# SenseBox-MCU-2-1.net
KiCad netlist of a schematic drawn in EAGLE
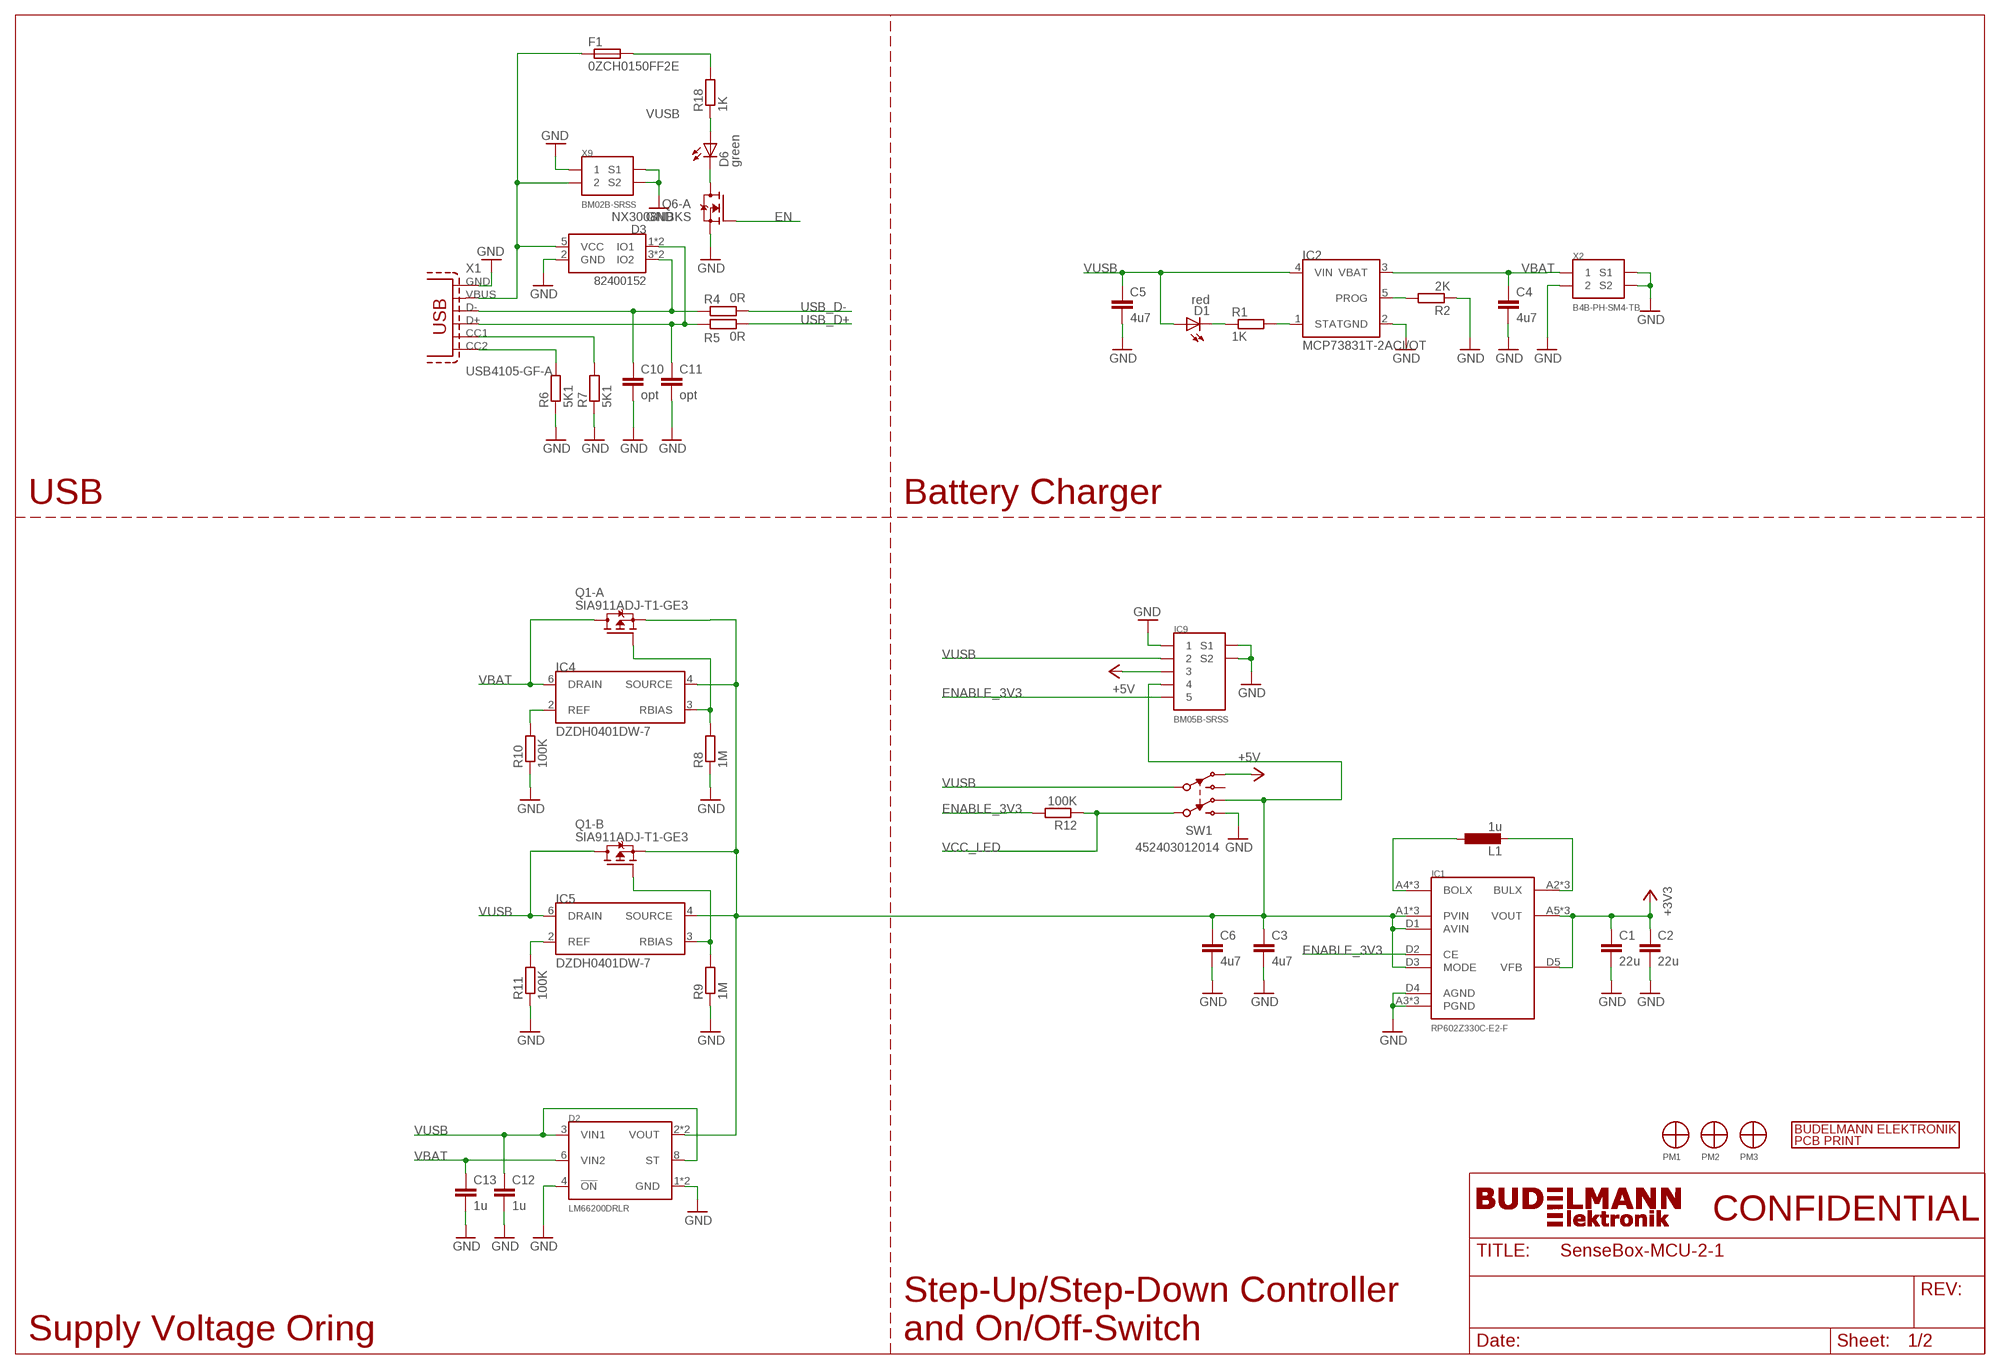
[diagram p0: schematic, sheet 1]
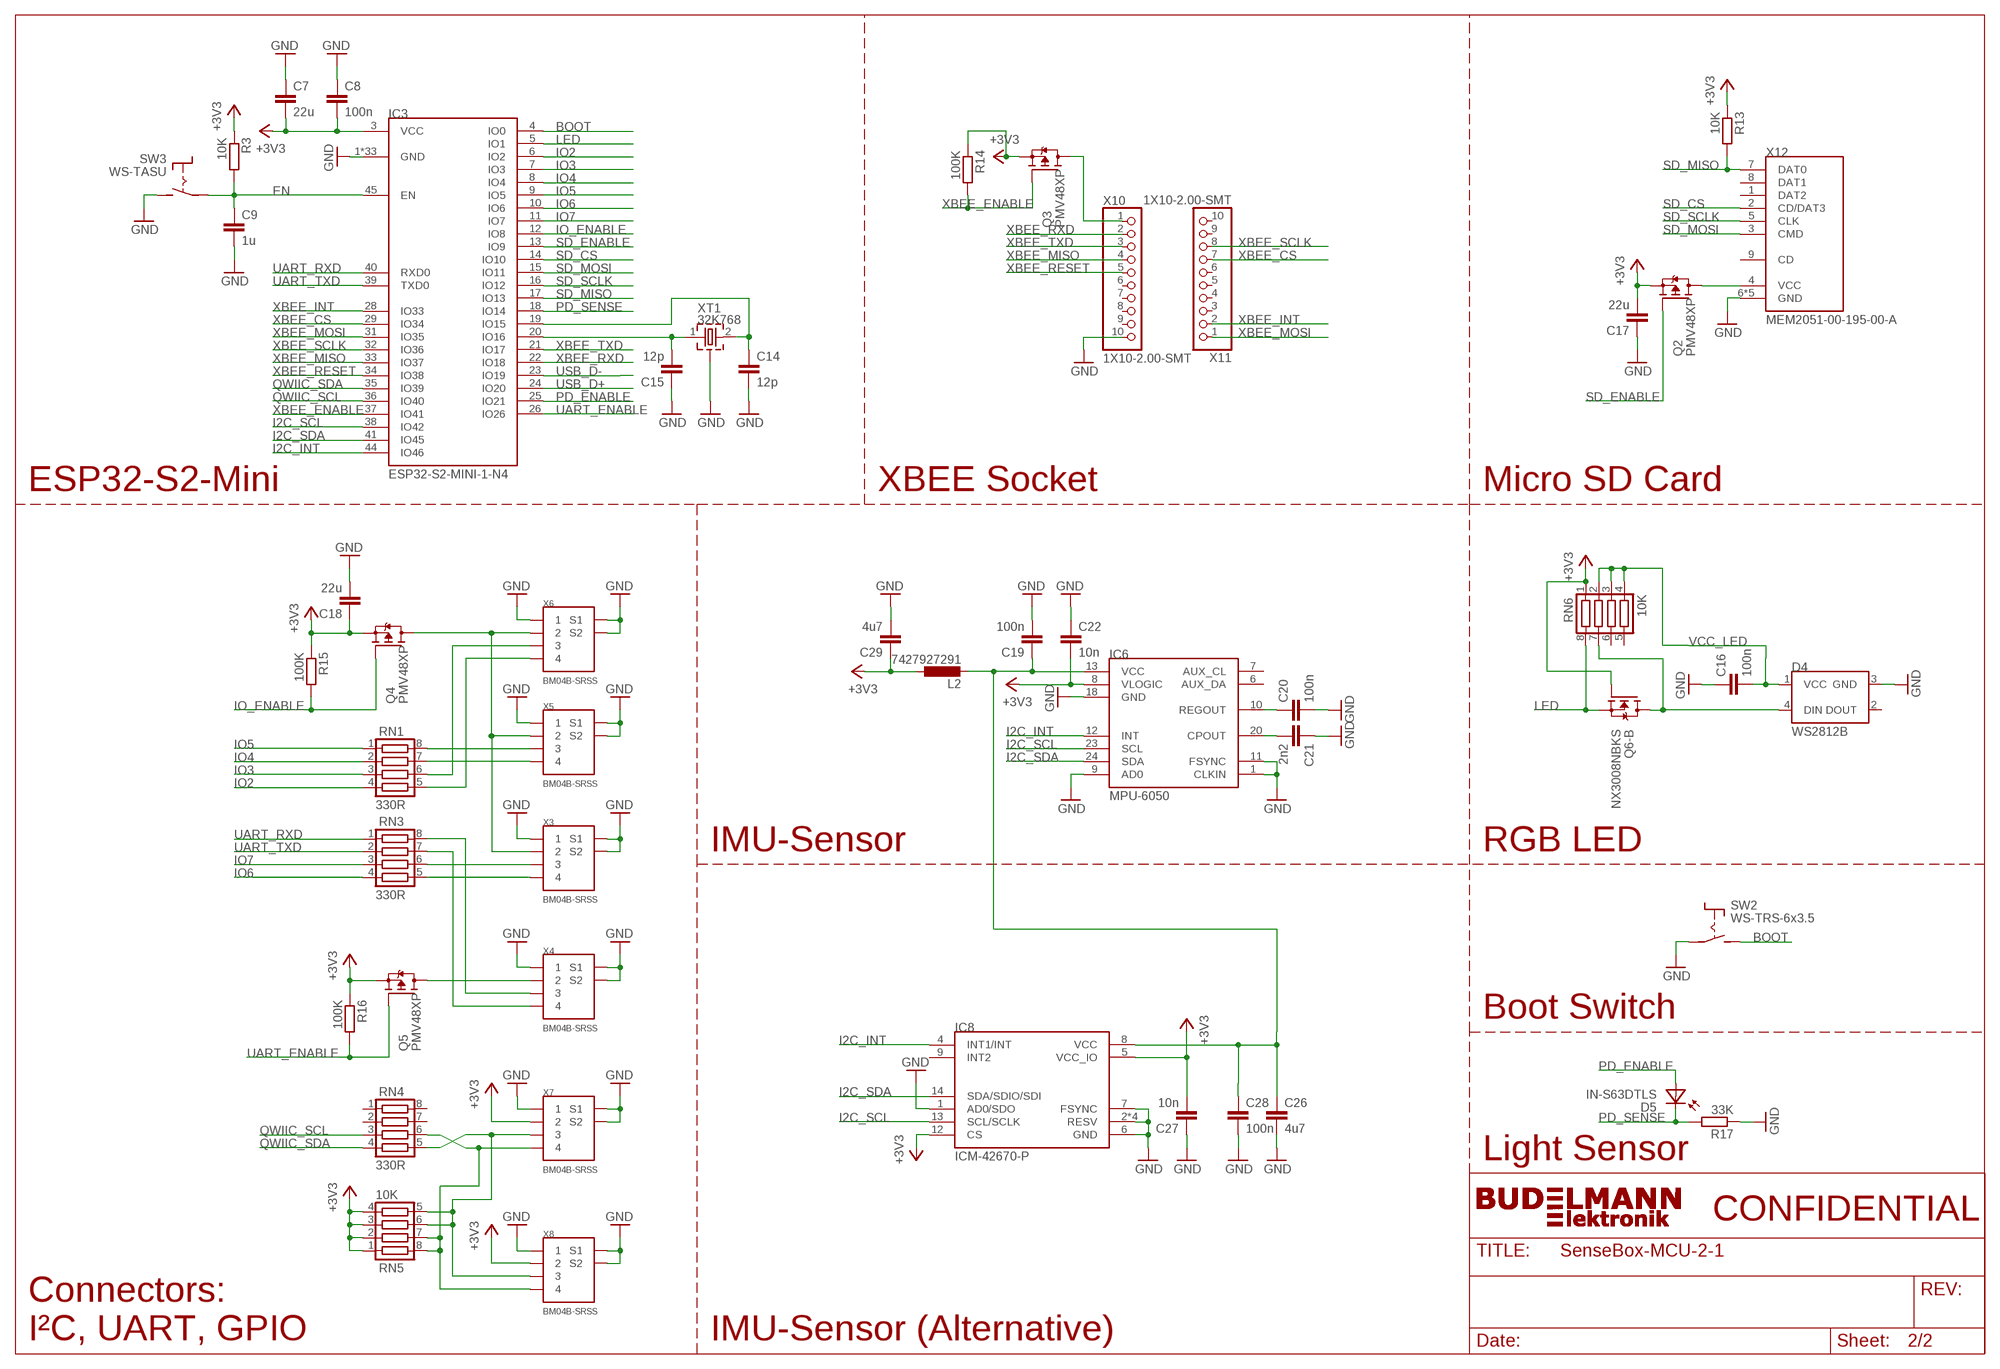
[diagram p1: schematic, sheet 2]

(export (version "E")
  (design (tool "Eeschema 10.0.6"))
  (components
    (comp (ref "C7")
      (value "22u")
      (footprint "eagle-import:0805N")
      (fields (field (name "VOLTAGE") "6V3"))
      (libsource (lib "eagle-import") (part "C_0805N_22U"))
    )
    (comp (ref "C8")
      (value "100n")
      (footprint "eagle-import:0402N")
      (fields (field (name "VOLTAGE") "16"))
      (libsource (lib "eagle-import") (part "C_0402N_100N"))
    )
    (comp (ref "C9")
      (value "1u")
      (footprint "eagle-import:0402N")
      (fields (field (name "VOLTAGE") "10"))
      (libsource (lib "eagle-import") (part "C_0402N_1U"))
    )
    (comp (ref "C14")
      (value "12p")
      (footprint "eagle-import:0402N")
      (fields (field (name "VOLTAGE") "50"))
      (libsource (lib "eagle-import") (part "C_0402N_12P"))
    )
    (comp (ref "C15")
      (value "12p")
      (footprint "eagle-import:0402N")
      (fields (field (name "VOLTAGE") "50"))
      (libsource (lib "eagle-import") (part "C_0402N_12P"))
    )
    (comp (ref "C16")
      (value "100n")
      (footprint "eagle-import:0402N")
      (fields (field (name "VOLTAGE") "16"))
      (libsource (lib "eagle-import") (part "C_0402N_100N"))
    )
    (comp (ref "C17")
      (value "22u")
      (footprint "eagle-import:0805N")
      (fields (field (name "VOLTAGE") "6V3"))
      (libsource (lib "eagle-import") (part "C_0805N_22U"))
    )
    (comp (ref "C18")
      (value "22u")
      (footprint "eagle-import:0805N")
      (fields (field (name "VOLTAGE") "6V3"))
      (libsource (lib "eagle-import") (part "C_0805N_22U"))
    )
    (comp (ref "C19")
      (value "100n")
      (footprint "eagle-import:0402N")
      (fields (field (name "VOLTAGE") "16"))
      (libsource (lib "eagle-import") (part "C_0402N_100N"))
    )
    (comp (ref "C20")
      (value "100n")
      (footprint "eagle-import:0402N")
      (fields (field (name "VOLTAGE") "16"))
      (libsource (lib "eagle-import") (part "C_0402N_100N"))
    )
    (comp (ref "C21")
      (value "2n2")
      (footprint "eagle-import:0402N")
      (fields (field (name "VOLTAGE") "50"))
      (libsource (lib "eagle-import") (part "C_0402N_2N2"))
    )
    (comp (ref "C22")
      (value "10n")
      (footprint "eagle-import:0402N")
      (fields (field (name "VOLTAGE") "25"))
      (libsource (lib "eagle-import") (part "C_0402N_10N"))
    )
    (comp (ref "C26")
      (value "4u7")
      (footprint "eagle-import:0603N")
      (fields (field (name "VOLTAGE") "6V3"))
      (libsource (lib "eagle-import") (part "C_0603N_4U7"))
    )
    (comp (ref "C27")
      (value "10n")
      (footprint "eagle-import:0402N")
      (fields (field (name "VOLTAGE") "25"))
      (libsource (lib "eagle-import") (part "C_0402N_10N"))
    )
    (comp (ref "C28")
      (value "100n")
      (footprint "eagle-import:0402N")
      (fields (field (name "VOLTAGE") "16"))
      (libsource (lib "eagle-import") (part "C_0402N_100N"))
    )
    (comp (ref "C29")
      (value "4u7")
      (footprint "eagle-import:0603N")
      (fields (field (name "VOLTAGE") "6V3"))
      (libsource (lib "eagle-import") (part "C_0603N_4U7"))
    )
    (comp (ref "D4")
      (value "WS2812B")
      (footprint "eagle-import:5050")
      (libsource (lib "eagle-import") (part "LED-ADRESSABLE_5050_WS2812B"))
    )
    (comp (ref "D5")
      (value "IN-S63DTLS")
      (footprint "eagle-import:0603N")
      (libsource (lib "eagle-import") (part "PHOTODIODE_0603N_IN-S63DTLS"))
    )
    (comp (ref "IC3")
      (value "ESP32-S2-MINI-1-N4")
      (footprint "eagle-import:ESP32-S2-MINI")
      (libsource (lib "eagle-import") (part "ESP32-S2-MINI_ESP32-S2-MINI_ESP32-S2-MINI-1-N4"))
    )
    (comp (ref "IC6")
      (value "MPU-6050")
      (footprint "eagle-import:QFN24_4X4")
      (libsource (lib "eagle-import") (part "MPU-6050"))
    )
    (comp (ref "IC8")
      (value "ICM-42670-P")
      (footprint "eagle-import:LGA14_2.5X3")
      (libsource (lib "eagle-import") (part "ICM-42670-P_LGA14_2.5X3"))
    )
    (comp (ref "L2")
      (value "7427927291")
      (footprint "eagle-import:0402N")
      (libsource (lib "eagle-import") (part "L_0402N_WE-CBF-7427927291"))
    )
    (comp (ref "Q2")
      (value "PMV48XP")
      (footprint "eagle-import:SOT23")
      (fields (field (name "VOLTAGE") "20"))
      (libsource (lib "eagle-import") (part "MOSFET-P_SOT23'_PMV48XP"))
    )
    (comp (ref "Q3")
      (value "PMV48XP")
      (footprint "eagle-import:SOT23")
      (fields (field (name "VOLTAGE") "20"))
      (libsource (lib "eagle-import") (part "MOSFET-P_SOT23'_PMV48XP"))
    )
    (comp (ref "Q4")
      (value "PMV48XP")
      (footprint "eagle-import:SOT23")
      (fields (field (name "VOLTAGE") "20"))
      (libsource (lib "eagle-import") (part "MOSFET-P_SOT23'_PMV48XP"))
    )
    (comp (ref "Q5")
      (value "PMV48XP")
      (footprint "eagle-import:SOT23")
      (fields (field (name "VOLTAGE") "20"))
      (libsource (lib "eagle-import") (part "MOSFET-P_SOT23'_PMV48XP"))
    )
    (comp (ref "Q6")
      (value "NX3008NBKS")
      (footprint "eagle-import:SOT363")
      (fields (field (name "POWER") "0.3") (field (name "VOLTAGE") "30"))
      (libsource (lib "eagle-import") (part "MOSFET-N-DUAL_SOT363_NX3008NBKS"))
    )
    (comp (ref "R3")
      (value "10K")
      (footprint "eagle-import:0402N")
      (fields (field (name "POWER") "0.063") (field (name "TOLERANCE") "1%") (field (name "VOLTAGE") "50"))
      (libsource (lib "eagle-import") (part "R_0402N_10K"))
    )
    (comp (ref "R13")
      (value "10K")
      (footprint "eagle-import:0402N")
      (fields (field (name "POWER") "0.063") (field (name "TOLERANCE") "1%") (field (name "VOLTAGE") "50"))
      (libsource (lib "eagle-import") (part "R_0402N_10K"))
    )
    (comp (ref "R14")
      (value "100K")
      (footprint "eagle-import:0402N")
      (fields (field (name "POWER") "0.063") (field (name "TOLERANCE") "1%") (field (name "VOLTAGE") "50"))
      (libsource (lib "eagle-import") (part "R_0402N_100K"))
    )
    (comp (ref "R15")
      (value "100K")
      (footprint "eagle-import:0402N")
      (fields (field (name "POWER") "0.063") (field (name "TOLERANCE") "1%") (field (name "VOLTAGE") "50"))
      (libsource (lib "eagle-import") (part "R_0402N_100K"))
    )
    (comp (ref "R16")
      (value "100K")
      (footprint "eagle-import:0402N")
      (fields (field (name "POWER") "0.063") (field (name "TOLERANCE") "1%") (field (name "VOLTAGE") "50"))
      (libsource (lib "eagle-import") (part "R_0402N_100K"))
    )
    (comp (ref "R17")
      (value "33K")
      (footprint "eagle-import:0402N")
      (fields (field (name "POWER") "0.063") (field (name "TOLERANCE") "1%") (field (name "VOLTAGE") "50"))
      (libsource (lib "eagle-import") (part "R_0402N_33K"))
    )
    (comp (ref "RN1")
      (value "330R")
      (footprint "eagle-import:CAY16")
      (fields (field (name "POWER") "0.062") (field (name "TOLERANCE") "5%") (field (name "VOLTAGE") "50"))
      (libsource (lib "eagle-import") (part "RN4_CAY16_330R"))
    )
    (comp (ref "RN3")
      (value "330R")
      (footprint "eagle-import:CAY16")
      (fields (field (name "POWER") "0.062") (field (name "TOLERANCE") "5%") (field (name "VOLTAGE") "50"))
      (libsource (lib "eagle-import") (part "RN4_CAY16_330R"))
    )
    (comp (ref "RN4")
      (value "330R")
      (footprint "eagle-import:CAY16")
      (fields (field (name "POWER") "0.062") (field (name "TOLERANCE") "5%") (field (name "VOLTAGE") "50"))
      (libsource (lib "eagle-import") (part "RN4_CAY16_330R"))
    )
    (comp (ref "RN5")
      (value "10K")
      (footprint "eagle-import:CAY16")
      (fields (field (name "POWER") "0.062") (field (name "TOLERANCE") "5%") (field (name "VOLTAGE") "50"))
      (libsource (lib "eagle-import") (part "RN4_CAY16_10K"))
    )
    (comp (ref "RN6")
      (value "10K")
      (footprint "eagle-import:CAY16")
      (fields (field (name "POWER") "0.062") (field (name "TOLERANCE") "5%") (field (name "VOLTAGE") "50"))
      (libsource (lib "eagle-import") (part "RN4_CAY16_10K"))
    )
    (comp (ref "SW2")
      (value "WS-TRS-6x3.5")
      (footprint "eagle-import:WS-TRS-6X3.5")
      (libsource (lib "eagle-import") (part "TACTILE_SWITCH_WS-TRS-6X3.5"))
    )
    (comp (ref "SW3")
      (value "WS-TASU")
      (footprint "eagle-import:WS-TASU")
      (libsource (lib "eagle-import") (part "TACTILE_SWITCH_WS-TASU"))
    )
    (comp (ref "X3")
      (value "BM04B-SRSS")
      (footprint "eagle-import:BM04B-SRSS")
      (libsource (lib "eagle-import") (part "SH-04_BM04B-SRSS_BM04B-SRSS"))
    )
    (comp (ref "X4")
      (value "BM04B-SRSS")
      (footprint "eagle-import:BM04B-SRSS")
      (libsource (lib "eagle-import") (part "SH-04_BM04B-SRSS_BM04B-SRSS"))
    )
    (comp (ref "X5")
      (value "BM04B-SRSS")
      (footprint "eagle-import:BM04B-SRSS")
      (libsource (lib "eagle-import") (part "SH-04_BM04B-SRSS_BM04B-SRSS"))
    )
    (comp (ref "X6")
      (value "BM04B-SRSS")
      (footprint "eagle-import:BM04B-SRSS")
      (libsource (lib "eagle-import") (part "SH-04_BM04B-SRSS_BM04B-SRSS"))
    )
    (comp (ref "X7")
      (value "BM04B-SRSS")
      (footprint "eagle-import:BM04B-SRSS")
      (libsource (lib "eagle-import") (part "SH-04_BM04B-SRSS_BM04B-SRSS"))
    )
    (comp (ref "X8")
      (value "BM04B-SRSS")
      (footprint "eagle-import:BM04B-SRSS")
      (libsource (lib "eagle-import") (part "SH-04_BM04B-SRSS_BM04B-SRSS"))
    )
    (comp (ref "X10")
      (value "1X10-2.00-SMT")
      (footprint "eagle-import:1X10-2.00-SMD")
      (libsource (lib "eagle-import") (part "1X10_2.00-SMT"))
    )
    (comp (ref "X11")
      (value "1X10-2.00-SMT")
      (footprint "eagle-import:1X10-2.00-SMD")
      (libsource (lib "eagle-import") (part "1X10_2.00-SMT"))
    )
    (comp (ref "X12")
      (value "MEM2051-00-195-00-A")
      (footprint "eagle-import:MEM2051")
      (libsource (lib "eagle-import") (part "SD-CARD2_MEM2051"))
    )
    (comp (ref "XT1")
      (value "32K768")
      (footprint "eagle-import:1.4X1.5X5.2")
      (libsource (lib "eagle-import") (part "CRYSTAL-1GND_1.4X1.5X5.2"))
    )
    (comp (ref "C1")
      (value "22u")
      (footprint "eagle-import:0805N")
      (fields (field (name "VOLTAGE") "6V3"))
      (libsource (lib "eagle-import") (part "C_0805N_22U"))
    )
    (comp (ref "C2")
      (value "22u")
      (footprint "eagle-import:0805N")
      (fields (field (name "VOLTAGE") "6V3"))
      (libsource (lib "eagle-import") (part "C_0805N_22U"))
    )
    (comp (ref "C3")
      (value "4u7")
      (footprint "eagle-import:0603N")
      (fields (field (name "VOLTAGE") "6V3"))
      (libsource (lib "eagle-import") (part "C_0603N_4U7"))
    )
    (comp (ref "C4")
      (value "4u7")
      (footprint "eagle-import:0603N")
      (fields (field (name "VOLTAGE") "6V3"))
      (libsource (lib "eagle-import") (part "C_0603N_4U7"))
    )
    (comp (ref "C5")
      (value "4u7")
      (footprint "eagle-import:0603N")
      (fields (field (name "VOLTAGE") "6V3"))
      (libsource (lib "eagle-import") (part "C_0603N_4U7"))
    )
    (comp (ref "C6")
      (value "4u7")
      (footprint "eagle-import:0603N")
      (fields (field (name "VOLTAGE") "6V3"))
      (libsource (lib "eagle-import") (part "C_0603N_4U7"))
    )
    (comp (ref "C10")
      (value "opt")
      (footprint "eagle-import:0402N")
      (libsource (lib "eagle-import") (part "C_0402N"))
    )
    (comp (ref "C11")
      (value "opt")
      (footprint "eagle-import:0402N")
      (libsource (lib "eagle-import") (part "C_0402N"))
    )
    (comp (ref "C12")
      (value "1u")
      (footprint "eagle-import:0402N")
      (fields (field (name "VOLTAGE") "10"))
      (libsource (lib "eagle-import") (part "C_0402N_1U"))
    )
    (comp (ref "C13")
      (value "1u")
      (footprint "eagle-import:0402N")
      (fields (field (name "VOLTAGE") "10"))
      (libsource (lib "eagle-import") (part "C_0402N_1U"))
    )
    (comp (ref "D1")
      (value "red")
      (footprint "eagle-import:0603N")
      (libsource (lib "eagle-import") (part "LED_0603N_RED"))
    )
    (comp (ref "D2")
      (value "LM66200DRLR")
      (footprint "eagle-import:SOT-5X3")
      (libsource (lib "eagle-import") (part "LM66200"))
    )
    (comp (ref "D3")
      (value "82400152")
      (footprint "eagle-import:SOT563")
      (libsource (lib "eagle-import") (part "TVS-3-CHANNELS_SOT563_WE-TVS"))
    )
    (comp (ref "D6")
      (value "green")
      (footprint "eagle-import:0603N")
      (libsource (lib "eagle-import") (part "LED_0603N_GREEN"))
    )
    (comp (ref "F1")
      (value "0ZCH0150FF2E")
      (footprint "eagle-import:1210N")
      (libsource (lib "eagle-import") (part "FUSE-2PIN_1210N_1.5A"))
    )
    (comp (ref "IC1")
      (value "RP602Z330C-E2-F")
      (footprint "eagle-import:WLCSP-20-P1")
      (libsource (lib "eagle-import") (part "RP602_WLCSP-20-P1_RP602Z330C-E2-F"))
    )
    (comp (ref "IC2")
      (value "MCP73831T-2ACI/OT")
      (footprint "eagle-import:SOT23-5")
      (libsource (lib "eagle-import") (part "MCP73831_SOT23-5_MCP73831T-2ACI/OT"))
    )
    (comp (ref "IC4")
      (value "DZDH0401DW-7")
      (footprint "eagle-import:SOT363")
      (libsource (lib "eagle-import") (part "DZDH0401DW"))
    )
    (comp (ref "IC5")
      (value "DZDH0401DW-7")
      (footprint "eagle-import:SOT363")
      (libsource (lib "eagle-import") (part "DZDH0401DW"))
    )
    (comp (ref "IC9")
      (value "BM05B-SRSS")
      (footprint "eagle-import:BM05B-SRSS")
      (libsource (lib "eagle-import") (part "SH-05_BM05B-SRSS_BM05B-SRSS"))
    )
    (comp (ref "L1")
      (value "1u")
      (footprint "eagle-import:5040")
      (libsource (lib "eagle-import") (part "L_5040_WE-LQS-1U"))
    )
    (comp (ref "PM1")
      (value "PM_ASSEMBLY")
      (footprint "eagle-import:PM1")
      (libsource (lib "eagle-import") (part "PM_ASSEMBLY"))
    )
    (comp (ref "PM2")
      (value "PM_ASSEMBLY")
      (footprint "eagle-import:PM1")
      (libsource (lib "eagle-import") (part "PM_ASSEMBLY"))
    )
    (comp (ref "PM3")
      (value "PM_ASSEMBLY")
      (footprint "eagle-import:PM1")
      (libsource (lib "eagle-import") (part "PM_ASSEMBLY"))
    )
    (comp (ref "Q1")
      (value "SIA911ADJ-T1-GE3")
      (footprint "eagle-import:POWERPAK-SC70-6")
      (fields (field (name "VOLTAGE") "20"))
      (libsource (lib "eagle-import") (part "MOSFET-P-DUAL_POWERPAK-SC70-6_SIA911ADJ-T1-GE3"))
    )
    (comp (ref "R1")
      (value "1K")
      (footprint "eagle-import:0402N")
      (fields (field (name "POWER") "0.063") (field (name "TOLERANCE") "1%") (field (name "VOLTAGE") "50"))
      (libsource (lib "eagle-import") (part "R_0402N_1K"))
    )
    (comp (ref "R2")
      (value "2K")
      (footprint "eagle-import:0402N")
      (fields (field (name "POWER") "0.063") (field (name "TOLERANCE") "1%") (field (name "VOLTAGE") "50"))
      (libsource (lib "eagle-import") (part "R_0402N_2K"))
    )
    (comp (ref "R4")
      (value "0R")
      (footprint "eagle-import:0402N")
      (libsource (lib "eagle-import") (part "R_0402N_0R"))
    )
    (comp (ref "R5")
      (value "0R")
      (footprint "eagle-import:0402N")
      (libsource (lib "eagle-import") (part "R_0402N_0R"))
    )
    (comp (ref "R6")
      (value "5K1")
      (footprint "eagle-import:0402N")
      (fields (field (name "POWER") "0.063") (field (name "TOLERANCE") "1%") (field (name "VOLTAGE") "50"))
      (libsource (lib "eagle-import") (part "R_0402N_5K1"))
    )
    (comp (ref "R7")
      (value "5K1")
      (footprint "eagle-import:0402N")
      (fields (field (name "POWER") "0.063") (field (name "TOLERANCE") "1%") (field (name "VOLTAGE") "50"))
      (libsource (lib "eagle-import") (part "R_0402N_5K1"))
    )
    (comp (ref "R8")
      (value "1M")
      (footprint "eagle-import:0402N")
      (fields (field (name "POWER") "0.063") (field (name "TOLERANCE") "1%") (field (name "VOLTAGE") "50"))
      (libsource (lib "eagle-import") (part "R_0402N_1M"))
    )
    (comp (ref "R9")
      (value "1M")
      (footprint "eagle-import:0402N")
      (fields (field (name "POWER") "0.063") (field (name "TOLERANCE") "1%") (field (name "VOLTAGE") "50"))
      (libsource (lib "eagle-import") (part "R_0402N_1M"))
    )
    (comp (ref "R10")
      (value "100K")
      (footprint "eagle-import:0402N")
      (fields (field (name "POWER") "0.063") (field (name "TOLERANCE") "1%") (field (name "VOLTAGE") "50"))
      (libsource (lib "eagle-import") (part "R_0402N_100K"))
    )
    (comp (ref "R11")
      (value "100K")
      (footprint "eagle-import:0402N")
      (fields (field (name "POWER") "0.063") (field (name "TOLERANCE") "1%") (field (name "VOLTAGE") "50"))
      (libsource (lib "eagle-import") (part "R_0402N_100K"))
    )
    (comp (ref "R12")
      (value "100K")
      (footprint "eagle-import:0402N")
      (fields (field (name "POWER") "0.063") (field (name "TOLERANCE") "1%") (field (name "VOLTAGE") "50"))
      (libsource (lib "eagle-import") (part "R_0402N_100K"))
    )
    (comp (ref "R18")
      (value "1K")
      (footprint "eagle-import:0402N")
      (fields (field (name "POWER") "0.063") (field (name "TOLERANCE") "1%") (field (name "VOLTAGE") "50"))
      (libsource (lib "eagle-import") (part "R_0402N_1K"))
    )
    (comp (ref "SW1")
      (value "452403012014")
      (footprint "eagle-import:WS-SLSV")
      (libsource (lib "eagle-import") (part "DPDT_WS-SLSV"))
    )
    (comp (ref "U$3")
      (value "BE_LOGO_10MM_T")
      (footprint "eagle-import:BE_TOP_10MM")
      (libsource (lib "eagle-import") (part "BE_LOGO_10MM_T"))
    )
    (comp (ref "X1")
      (value "USB4105-GF-A")
      (footprint "eagle-import:USB4105")
      (libsource (lib "eagle-import") (part "USB-C-2.0_USB4105_USB4105-GF-A"))
    )
    (comp (ref "X2")
      (value "B4B-PH-SM4-TB")
      (footprint "eagle-import:B4B-PH-SM4-TB")
      (libsource (lib "eagle-import") (part "SH-02_B4B-PH-SM4-TB_B4B-PH-SM4-TB"))
    )
    (comp (ref "X9")
      (value "BM02B-SRSS")
      (footprint "eagle-import:BM02B-SRSS")
      (libsource (lib "eagle-import") (part "SH-02_BM02B-SRSS_BM02B-SRSS"))
    )
  )
  (nets
    (net (code "1") (name "+3V3") (class "Default")
      (node (ref "C1") (pin "1") (pinfunction "1_1") (pintype "passive"))
      (node (ref "C17") (pin "2") (pinfunction "2_2") (pintype "passive"))
      (node (ref "C18") (pin "1") (pinfunction "1_1") (pintype "passive"))
      (node (ref "C2") (pin "1") (pinfunction "1_1") (pintype "passive"))
      (node (ref "C22") (pin "2") (pinfunction "2_2") (pintype "passive"))
      (node (ref "C27") (pin "2") (pinfunction "2_2") (pintype "passive"))
      (node (ref "C29") (pin "1") (pinfunction "1_1") (pintype "passive"))
      (node (ref "C7") (pin "2") (pinfunction "2_2") (pintype "passive"))
      (node (ref "C8") (pin "2") (pinfunction "2_2") (pintype "passive"))
      (node (ref "IC1") (pin "A5") (pinfunction "VOUT_A5") (pintype "power_in"))
      (node (ref "IC1") (pin "B5") (pinfunction "VOUT_B5") (pintype "power_in"))
      (node (ref "IC1") (pin "C5") (pinfunction "VOUT_C5") (pintype "power_in"))
      (node (ref "IC1") (pin "D5") (pinfunction "VFB_D5") (pintype "input"))
      (node (ref "IC3") (pin "3") (pinfunction "VCC_3") (pintype "power_in"))
      (node (ref "IC6") (pin "8") (pinfunction "VLOGIC_8") (pintype "power_in"))
      (node (ref "IC8") (pin "12") (pinfunction "CS_12") (pintype "input"))
      (node (ref "IC8") (pin "5") (pinfunction "VCC_IO_5") (pintype "power_in"))
      (node (ref "L2") (pin "1") (pinfunction "1_1") (pintype "passive"))
      (node (ref "Q2") (pin "2") (pinfunction "S_2") (pintype "passive"))
      (node (ref "Q3") (pin "2") (pinfunction "S_2") (pintype "passive"))
      (node (ref "Q4") (pin "2") (pinfunction "S_2") (pintype "passive"))
      (node (ref "Q5") (pin "2") (pinfunction "S_2") (pintype "passive"))
      (node (ref "Q6") (pin "5") (pinfunction "G_5") (pintype "passive"))
      (node (ref "R13") (pin "1") (pinfunction "1_1") (pintype "passive"))
      (node (ref "R14") (pin "1") (pinfunction "1_1") (pintype "passive"))
      (node (ref "R15") (pin "1") (pinfunction "1_1") (pintype "passive"))
      (node (ref "R16") (pin "1") (pinfunction "1_1") (pintype "passive"))
      (node (ref "R3") (pin "1") (pinfunction "1_1") (pintype "passive"))
      (node (ref "RN5") (pin "1") (pinfunction "1_1") (pintype "passive"))
      (node (ref "RN5") (pin "2") (pinfunction "2_2") (pintype "passive"))
      (node (ref "RN5") (pin "3") (pinfunction "3_3") (pintype "passive"))
      (node (ref "RN5") (pin "4") (pinfunction "4_4") (pintype "passive"))
      (node (ref "RN6") (pin "1") (pinfunction "1_1") (pintype "passive"))
      (node (ref "X7") (pin "2") (pinfunction "2_2") (pintype "bidirectional"))
      (node (ref "X8") (pin "2") (pinfunction "2_2") (pintype "bidirectional"))
    )
    (net (code "2") (name "+5V") (class "Default")
      (node (ref "IC9") (pin "3") (pinfunction "3_3") (pintype "bidirectional"))
      (node (ref "SW1") (pin "3") (pinfunction "NC1_3") (pintype "bidirectional"))
    )
    (net (code "3") (name "BOOT") (class "Default")
      (node (ref "IC3") (pin "4") (pinfunction "IO0_4") (pintype "bidirectional"))
      (node (ref "SW2") (pin "2") (pinfunction "S_2") (pintype "passive"))
    )
    (net (code "4") (name "EN") (class "Default")
      (node (ref "C9") (pin "1") (pinfunction "1_1") (pintype "passive"))
      (node (ref "IC3") (pin "45") (pinfunction "EN_45") (pintype "input"))
      (node (ref "Q6") (pin "2") (pinfunction "G_2") (pintype "passive"))
      (node (ref "R3") (pin "2") (pinfunction "2_2") (pintype "passive"))
      (node (ref "SW3") (pin "1") (pinfunction "P_1") (pintype "passive"))
      (node (ref "SW3") (pin "3") (pinfunction "P_3") (pintype "passive"))
    )
    (net (code "5") (name "ENABLE_3V3") (class "Default")
      (node (ref "IC1") (pin "D2") (pinfunction "CE_D2") (pintype "input"))
      (node (ref "IC9") (pin "5") (pinfunction "5_5") (pintype "bidirectional"))
      (node (ref "R12") (pin "2") (pinfunction "2_2") (pintype "passive"))
    )
    (net (code "6") (name "GND") (class "Default")
      (node (ref "C1") (pin "2") (pinfunction "2_2") (pintype "passive"))
      (node (ref "C10") (pin "2") (pinfunction "2_2") (pintype "passive"))
      (node (ref "C11") (pin "2") (pinfunction "2_2") (pintype "passive"))
      (node (ref "C12") (pin "2") (pinfunction "2_2") (pintype "passive"))
      (node (ref "C13") (pin "2") (pinfunction "2_2") (pintype "passive"))
      (node (ref "C14") (pin "2") (pinfunction "2_2") (pintype "passive"))
      (node (ref "C15") (pin "1") (pinfunction "1_1") (pintype "passive"))
      (node (ref "C16") (pin "1") (pinfunction "1_1") (pintype "passive"))
      (node (ref "C17") (pin "1") (pinfunction "1_1") (pintype "passive"))
      (node (ref "C18") (pin "2") (pinfunction "2_2") (pintype "passive"))
      (node (ref "C19") (pin "2") (pinfunction "2_2") (pintype "passive"))
      (node (ref "C2") (pin "2") (pinfunction "2_2") (pintype "passive"))
      (node (ref "C20") (pin "2") (pinfunction "2_2") (pintype "passive"))
      (node (ref "C21") (pin "1") (pinfunction "1_1") (pintype "passive"))
      (node (ref "C22") (pin "1") (pinfunction "1_1") (pintype "passive"))
      (node (ref "C26") (pin "2") (pinfunction "2_2") (pintype "passive"))
      (node (ref "C27") (pin "1") (pinfunction "1_1") (pintype "passive"))
      (node (ref "C28") (pin "2") (pinfunction "2_2") (pintype "passive"))
      (node (ref "C29") (pin "2") (pinfunction "2_2") (pintype "passive"))
      (node (ref "C3") (pin "2") (pinfunction "2_2") (pintype "passive"))
      (node (ref "C4") (pin "2") (pinfunction "2_2") (pintype "passive"))
      (node (ref "C5") (pin "2") (pinfunction "2_2") (pintype "passive"))
      (node (ref "C6") (pin "2") (pinfunction "2_2") (pintype "passive"))
      (node (ref "C7") (pin "1") (pinfunction "1_1") (pintype "passive"))
      (node (ref "C8") (pin "1") (pinfunction "1_1") (pintype "passive"))
      (node (ref "C9") (pin "2") (pinfunction "2_2") (pintype "passive"))
      (node (ref "D2") (pin "1") (pinfunction "GND_1") (pintype "power_in"))
      (node (ref "D2") (pin "4") (pinfunction "~{ON}_4") (pintype "input"))
      (node (ref "D2") (pin "5") (pinfunction "GND_5") (pintype "power_in"))
      (node (ref "D3") (pin "2") (pinfunction "GND_2") (pintype "power_in"))
      (node (ref "D4") (pin "3") (pinfunction "GND_3") (pintype "power_in"))
      (node (ref "IC1") (pin "A3") (pinfunction "PGND_A3") (pintype "power_in"))
      (node (ref "IC1") (pin "B3") (pinfunction "PGND_B3") (pintype "power_in"))
      (node (ref "IC1") (pin "C3") (pinfunction "PGND_C3") (pintype "power_in"))
      (node (ref "IC1") (pin "D4") (pinfunction "AGND_D4") (pintype "power_in"))
      (node (ref "IC2") (pin "2") (pinfunction "GND_2") (pintype "power_in"))
      (node (ref "IC3") (pin "1") (pinfunction "GND_1") (pintype "power_in"))
      (node (ref "IC3") (pin "2") (pinfunction "GND_2") (pintype "power_in"))
      (node (ref "IC3") (pin "30") (pinfunction "GND_30") (pintype "power_in"))
      (node (ref "IC3") (pin "42") (pinfunction "GND_42") (pintype "power_in"))
      (node (ref "IC3") (pin "43") (pinfunction "GND_43") (pintype "power_in"))
      (node (ref "IC3") (pin "46") (pinfunction "GND_46") (pintype "power_in"))
      (node (ref "IC3") (pin "47") (pinfunction "GND_47") (pintype "power_in"))
      (node (ref "IC3") (pin "48") (pinfunction "GND_48") (pintype "power_in"))
      (node (ref "IC3") (pin "49") (pinfunction "GND_49") (pintype "power_in"))
      (node (ref "IC3") (pin "50") (pinfunction "GND_50") (pintype "power_in"))
      (node (ref "IC3") (pin "51") (pinfunction "GND_51") (pintype "power_in"))
      (node (ref "IC3") (pin "52") (pinfunction "GND_52") (pintype "power_in"))
      (node (ref "IC3") (pin "53") (pinfunction "GND_53") (pintype "power_in"))
      (node (ref "IC3") (pin "54") (pinfunction "GND_54") (pintype "power_in"))
      (node (ref "IC3") (pin "55") (pinfunction "GND_55") (pintype "power_in"))
      (node (ref "IC3") (pin "56") (pinfunction "GND_56") (pintype "power_in"))
      (node (ref "IC3") (pin "57") (pinfunction "GND_57") (pintype "power_in"))
      (node (ref "IC3") (pin "58") (pinfunction "GND_58") (pintype "power_in"))
      (node (ref "IC3") (pin "59") (pinfunction "GND_59") (pintype "power_in"))
      (node (ref "IC3") (pin "60") (pinfunction "GND_60") (pintype "power_in"))
      (node (ref "IC3") (pin "61") (pinfunction "GND_61") (pintype "power_in"))
      (node (ref "IC3") (pin "62") (pinfunction "GND_62") (pintype "power_in"))
      (node (ref "IC3") (pin "63") (pinfunction "GND_63") (pintype "power_in"))
      (node (ref "IC3") (pin "64") (pinfunction "GND_64") (pintype "power_in"))
      (node (ref "IC3") (pin "65") (pinfunction "GND_65") (pintype "power_in"))
      (node (ref "IC3") (pin "66") (pinfunction "GND_66") (pintype "power_in"))
      (node (ref "IC3") (pin "67") (pinfunction "GND_67") (pintype "power_in"))
      (node (ref "IC3") (pin "68") (pinfunction "GND_68") (pintype "power_in"))
      (node (ref "IC3") (pin "69") (pinfunction "GND_69") (pintype "power_in"))
      (node (ref "IC3") (pin "70") (pinfunction "GND_70") (pintype "power_in"))
      (node (ref "IC3") (pin "71") (pinfunction "GND_71") (pintype "power_in"))
      (node (ref "IC3") (pin "72") (pinfunction "GND_72") (pintype "power_in"))
      (node (ref "IC3") (pin "73") (pinfunction "GND_73") (pintype "power_in"))
      (node (ref "IC6") (pin "1") (pinfunction "CLKIN_1") (pintype "input"))
      (node (ref "IC6") (pin "11") (pinfunction "FSYNC_11") (pintype "input"))
      (node (ref "IC6") (pin "18") (pinfunction "GND_18") (pintype "power_in"))
      (node (ref "IC6") (pin "9") (pinfunction "AD0_9") (pintype "input"))
      (node (ref "IC8") (pin "1") (pinfunction "AD0/SDO_1") (pintype "bidirectional"))
      (node (ref "IC8") (pin "10") (pinfunction "RESV_10") (pintype "power_in"))
      (node (ref "IC8") (pin "11") (pinfunction "RESV_11") (pintype "power_in"))
      (node (ref "IC8") (pin "2") (pinfunction "RESV_2") (pintype "power_in"))
      (node (ref "IC8") (pin "3") (pinfunction "RESV_3") (pintype "power_in"))
      (node (ref "IC8") (pin "6") (pinfunction "GND_6") (pintype "power_in"))
      (node (ref "IC8") (pin "7") (pinfunction "FSYNC_7") (pintype "input"))
      (node (ref "IC9") (pin "1") (pinfunction "1_1") (pintype "bidirectional"))
      (node (ref "IC9") (pin "S1") (pinfunction "S1_S1") (pintype "bidirectional"))
      (node (ref "IC9") (pin "S2") (pinfunction "S2_S2") (pintype "bidirectional"))
      (node (ref "Q6") (pin "1") (pinfunction "S_1") (pintype "passive"))
      (node (ref "R10") (pin "1") (pinfunction "1_1") (pintype "passive"))
      (node (ref "R11") (pin "1") (pinfunction "1_1") (pintype "passive"))
      (node (ref "R17") (pin "1") (pinfunction "1_1") (pintype "passive"))
      (node (ref "R2") (pin "1") (pinfunction "1_1") (pintype "passive"))
      (node (ref "R6") (pin "1") (pinfunction "1_1") (pintype "passive"))
      (node (ref "R7") (pin "1") (pinfunction "1_1") (pintype "passive"))
      (node (ref "R8") (pin "1") (pinfunction "1_1") (pintype "passive"))
      (node (ref "R9") (pin "1") (pinfunction "1_1") (pintype "passive"))
      (node (ref "SW1") (pin "4") (pinfunction "NO2_4") (pintype "bidirectional"))
      (node (ref "SW2") (pin "1") (pinfunction "P_1") (pintype "passive"))
      (node (ref "SW3") (pin "2") (pinfunction "S_2") (pintype "passive"))
      (node (ref "SW3") (pin "4") (pinfunction "S_4") (pintype "passive"))
      (node (ref "X1") (pin "A1_B12") (pinfunction "GND_A1_B12") (pintype "power_in"))
      (node (ref "X1") (pin "B1_A12") (pinfunction "GND_B1_A12") (pintype "power_in"))
      (node (ref "X1") (pin "S1") (pinfunction "GND_S1") (pintype "power_in"))
      (node (ref "X1") (pin "S2") (pinfunction "GND_S2") (pintype "power_in"))
      (node (ref "X1") (pin "S3") (pinfunction "GND_S3") (pintype "power_in"))
      (node (ref "X1") (pin "S4") (pinfunction "GND_S4") (pintype "power_in"))
      (node (ref "X10") (pin "10") (pinfunction "10_10") (pintype "passive"))
      (node (ref "X12") (pin "6") (pinfunction "GND_6") (pintype "power_in"))
      (node (ref "X12") (pin "S1") (pinfunction "GND_S1") (pintype "power_in"))
      (node (ref "X12") (pin "S2") (pinfunction "GND_S2") (pintype "power_in"))
      (node (ref "X12") (pin "S3") (pinfunction "GND_S3") (pintype "power_in"))
      (node (ref "X12") (pin "S4") (pinfunction "GND_S4") (pintype "power_in"))
      (node (ref "X2") (pin "2") (pinfunction "2_2") (pintype "bidirectional"))
      (node (ref "X2") (pin "SH1") (pinfunction "S1_SH1") (pintype "bidirectional"))
      (node (ref "X2") (pin "SH2") (pinfunction "S2_SH2") (pintype "bidirectional"))
      (node (ref "X3") (pin "1") (pinfunction "1_1") (pintype "bidirectional"))
      (node (ref "X3") (pin "S1") (pinfunction "S1_S1") (pintype "bidirectional"))
      (node (ref "X3") (pin "S2") (pinfunction "S2_S2") (pintype "bidirectional"))
      (node (ref "X4") (pin "1") (pinfunction "1_1") (pintype "bidirectional"))
      (node (ref "X4") (pin "S1") (pinfunction "S1_S1") (pintype "bidirectional"))
      (node (ref "X4") (pin "S2") (pinfunction "S2_S2") (pintype "bidirectional"))
      (node (ref "X5") (pin "1") (pinfunction "1_1") (pintype "bidirectional"))
      (node (ref "X5") (pin "S1") (pinfunction "S1_S1") (pintype "bidirectional"))
      (node (ref "X5") (pin "S2") (pinfunction "S2_S2") (pintype "bidirectional"))
      (node (ref "X6") (pin "1") (pinfunction "1_1") (pintype "bidirectional"))
      (node (ref "X6") (pin "S1") (pinfunction "S1_S1") (pintype "bidirectional"))
      (node (ref "X6") (pin "S2") (pinfunction "S2_S2") (pintype "bidirectional"))
      (node (ref "X7") (pin "1") (pinfunction "1_1") (pintype "bidirectional"))
      (node (ref "X7") (pin "S1") (pinfunction "S1_S1") (pintype "bidirectional"))
      (node (ref "X7") (pin "S2") (pinfunction "S2_S2") (pintype "bidirectional"))
      (node (ref "X8") (pin "1") (pinfunction "1_1") (pintype "bidirectional"))
      (node (ref "X8") (pin "S1") (pinfunction "S1_S1") (pintype "bidirectional"))
      (node (ref "X8") (pin "S2") (pinfunction "S2_S2") (pintype "bidirectional"))
      (node (ref "X9") (pin "1") (pinfunction "1_1") (pintype "bidirectional"))
      (node (ref "X9") (pin "S1") (pinfunction "S1_S1") (pintype "bidirectional"))
      (node (ref "X9") (pin "S2") (pinfunction "S2_S2") (pintype "bidirectional"))
      (node (ref "XT1") (pin "3") (pinfunction "GND_3") (pintype "power_in"))
    )
    (net (code "7") (name "I2C_INT") (class "Default")
      (node (ref "IC3") (pin "44") (pinfunction "IO46_44") (pintype "input"))
      (node (ref "IC6") (pin "12") (pinfunction "INT_12") (pintype "open_collector"))
      (node (ref "IC8") (pin "4") (pinfunction "INT1/INT_4") (pintype "output"))
    )
    (net (code "8") (name "I2C_SCL") (class "Default")
      (node (ref "IC3") (pin "38") (pinfunction "IO42_38") (pintype "bidirectional"))
      (node (ref "IC6") (pin "23") (pinfunction "SCL_23") (pintype "bidirectional"))
      (node (ref "IC8") (pin "13") (pinfunction "SCL/SCLK_13") (pintype "input"))
    )
    (net (code "9") (name "I2C_SDA") (class "Default")
      (node (ref "IC3") (pin "41") (pinfunction "IO45_41") (pintype "bidirectional"))
      (node (ref "IC6") (pin "24") (pinfunction "SDA_24") (pintype "bidirectional"))
      (node (ref "IC8") (pin "14") (pinfunction "SDA/SDIO/SDI_14") (pintype "bidirectional"))
    )
    (net (code "10") (name "IO2") (class "Default")
      (node (ref "IC3") (pin "6") (pinfunction "IO2_6") (pintype "bidirectional"))
      (node (ref "RN1") (pin "4") (pinfunction "4_4") (pintype "passive"))
    )
    (net (code "11") (name "IO3") (class "Default")
      (node (ref "IC3") (pin "7") (pinfunction "IO3_7") (pintype "bidirectional"))
      (node (ref "RN1") (pin "3") (pinfunction "3_3") (pintype "passive"))
    )
    (net (code "12") (name "IO4") (class "Default")
      (node (ref "IC3") (pin "8") (pinfunction "IO4_8") (pintype "bidirectional"))
      (node (ref "RN1") (pin "2") (pinfunction "2_2") (pintype "passive"))
    )
    (net (code "13") (name "IO5") (class "Default")
      (node (ref "IC3") (pin "9") (pinfunction "IO5_9") (pintype "bidirectional"))
      (node (ref "RN1") (pin "1") (pinfunction "1_1") (pintype "passive"))
    )
    (net (code "14") (name "IO6") (class "Default")
      (node (ref "IC3") (pin "10") (pinfunction "IO6_10") (pintype "bidirectional"))
      (node (ref "RN3") (pin "4") (pinfunction "4_4") (pintype "passive"))
    )
    (net (code "15") (name "IO7") (class "Default")
      (node (ref "IC3") (pin "11") (pinfunction "IO7_11") (pintype "bidirectional"))
      (node (ref "RN3") (pin "3") (pinfunction "3_3") (pintype "passive"))
    )
    (net (code "16") (name "IO_ENABLE") (class "Default")
      (node (ref "IC3") (pin "12") (pinfunction "IO8_12") (pintype "bidirectional"))
      (node (ref "Q4") (pin "1") (pinfunction "G_1") (pintype "passive"))
      (node (ref "R15") (pin "2") (pinfunction "2_2") (pintype "passive"))
    )
    (net (code "17") (name "LED") (class "Default")
      (node (ref "IC3") (pin "5") (pinfunction "IO1_5") (pintype "bidirectional"))
      (node (ref "Q6") (pin "4") (pinfunction "S_4") (pintype "passive"))
      (node (ref "RN6") (pin "8") (pinfunction "8_8") (pintype "passive"))
    )
    (net (code "18") (name "Net-(C10-Pad1)") (class "Default")
      (node (ref "C10") (pin "1") (pinfunction "1_1") (pintype "passive"))
      (node (ref "D3") (pin "3") (pinfunction "IO2_3") (pintype "passive"))
      (node (ref "D3") (pin "4") (pinfunction "IO2_4") (pintype "passive"))
      (node (ref "R4") (pin "1") (pinfunction "1_1") (pintype "passive"))
      (node (ref "X1") (pin "A7") (pinfunction "D-_A7") (pintype "bidirectional"))
      (node (ref "X1") (pin "B7") (pinfunction "D-_B7") (pintype "bidirectional"))
    )
    (net (code "19") (name "Net-(C11-Pad1)") (class "Default")
      (node (ref "C11") (pin "1") (pinfunction "1_1") (pintype "passive"))
      (node (ref "D3") (pin "1") (pinfunction "IO1_1") (pintype "passive"))
      (node (ref "D3") (pin "6") (pinfunction "IO1_6") (pintype "passive"))
      (node (ref "R5") (pin "1") (pinfunction "1_1") (pintype "passive"))
      (node (ref "X1") (pin "A6") (pinfunction "D+_A6") (pintype "bidirectional"))
      (node (ref "X1") (pin "B6") (pinfunction "D+_B6") (pintype "bidirectional"))
    )
    (net (code "20") (name "Net-(D1-PadC)") (class "Default")
      (node (ref "D1") (pin "C") (pinfunction "C_C") (pintype "passive"))
      (node (ref "R1") (pin "1") (pinfunction "1_1") (pintype "passive"))
    )
    (net (code "21") (name "Net-(D3-VCC)") (class "Default")
      (node (ref "D3") (pin "5") (pinfunction "VCC_5") (pintype "power_in"))
      (node (ref "F1") (pin "1") (pinfunction "2_1") (pintype "passive"))
      (node (ref "X1") (pin "A4_B9") (pinfunction "VBUS_A4_B9") (pintype "power_in"))
      (node (ref "X1") (pin "B4_A9") (pinfunction "VBUS_B4_A9") (pintype "power_in"))
      (node (ref "X9") (pin "2") (pinfunction "2_2") (pintype "bidirectional"))
    )
    (net (code "22") (name "Net-(D4-DIN)") (class "Default")
      (node (ref "D4") (pin "4") (pinfunction "DIN_4") (pintype "input"))
      (node (ref "Q6") (pin "3") (pinfunction "D_3") (pintype "passive"))
      (node (ref "RN6") (pin "7") (pinfunction "7_7") (pintype "passive"))
    )
    (net (code "23") (name "Net-(D6-PadA)") (class "Default")
      (node (ref "D6") (pin "A") (pinfunction "A_A") (pintype "passive"))
      (node (ref "R18") (pin "1") (pinfunction "1_1") (pintype "passive"))
    )
    (net (code "24") (name "Net-(IC1-AVIN)") (class "Default")
      (node (ref "C3") (pin "1") (pinfunction "1_1") (pintype "passive"))
      (node (ref "C6") (pin "1") (pinfunction "1_1") (pintype "passive"))
      (node (ref "D2") (pin "2") (pinfunction "VOUT_2") (pintype "power_in"))
      (node (ref "D2") (pin "7") (pinfunction "VOUT_7") (pintype "power_in"))
      (node (ref "IC1") (pin "A1") (pinfunction "PVIN_A1") (pintype "power_in"))
      (node (ref "IC1") (pin "B1") (pinfunction "PVIN_B1") (pintype "power_in"))
      (node (ref "IC1") (pin "C1") (pinfunction "PVIN_C1") (pintype "power_in"))
      (node (ref "IC1") (pin "D1") (pinfunction "AVIN_D1") (pintype "power_in"))
      (node (ref "IC1") (pin "D3") (pinfunction "MODE_D3") (pintype "input"))
      (node (ref "IC4") (pin "4") (pinfunction "SOURCE_4") (pintype "passive"))
      (node (ref "IC5") (pin "4") (pinfunction "SOURCE_4") (pintype "passive"))
      (node (ref "IC9") (pin "4") (pinfunction "4_4") (pintype "bidirectional"))
      (node (ref "Q1") (pin "1") (pinfunction "S_1") (pintype "passive"))
      (node (ref "Q1") (pin "4") (pinfunction "S_4") (pintype "passive"))
      (node (ref "SW1") (pin "6") (pinfunction "NC2_6") (pintype "bidirectional"))
    )
    (net (code "25") (name "Net-(IC1-BOLX-PadA4)") (class "Default")
      (node (ref "IC1") (pin "A4") (pinfunction "BOLX_A4") (pintype "output"))
      (node (ref "IC1") (pin "B4") (pinfunction "BOLX_B4") (pintype "output"))
      (node (ref "IC1") (pin "C4") (pinfunction "BOLX_C4") (pintype "output"))
      (node (ref "L1") (pin "1") (pinfunction "1_1") (pintype "passive"))
    )
    (net (code "26") (name "Net-(IC1-BULX-PadA2)") (class "Default")
      (node (ref "IC1") (pin "A2") (pinfunction "BULX_A2") (pintype "output"))
      (node (ref "IC1") (pin "B2") (pinfunction "BULX_B2") (pintype "output"))
      (node (ref "IC1") (pin "C2") (pinfunction "BULX_C2") (pintype "output"))
      (node (ref "L1") (pin "2") (pinfunction "2_2") (pintype "passive"))
    )
    (net (code "27") (name "Net-(IC2-PROG)") (class "Default")
      (node (ref "IC2") (pin "5") (pinfunction "PROG_5") (pintype "input"))
      (node (ref "R2") (pin "2") (pinfunction "2_2") (pintype "passive"))
    )
    (net (code "28") (name "Net-(IC2-STAT)") (class "Default")
      (node (ref "IC2") (pin "1") (pinfunction "STAT_1") (pintype "open_collector"))
      (node (ref "R1") (pin "2") (pinfunction "2_2") (pintype "passive"))
    )
    (net (code "29") (name "Net-(IC3-IO15)") (class "Default")
      (node (ref "C14") (pin "1") (pinfunction "1_1") (pintype "passive"))
      (node (ref "IC3") (pin "19") (pinfunction "IO15_19") (pintype "bidirectional"))
      (node (ref "XT1") (pin "2") (pinfunction "2_2") (pintype "passive"))
    )
    (net (code "30") (name "Net-(IC3-IO16)") (class "Default")
      (node (ref "C15") (pin "2") (pinfunction "2_2") (pintype "passive"))
      (node (ref "IC3") (pin "20") (pinfunction "IO16_20") (pintype "bidirectional"))
      (node (ref "XT1") (pin "1") (pinfunction "1_1") (pintype "passive"))
    )
    (net (code "31") (name "Net-(IC4-RBIAS)") (class "Default")
      (node (ref "IC4") (pin "3") (pinfunction "RBIAS_3") (pintype "passive"))
      (node (ref "Q1") (pin "2") (pinfunction "G_2") (pintype "passive"))
      (node (ref "R8") (pin "2") (pinfunction "2_2") (pintype "passive"))
    )
    (net (code "32") (name "Net-(IC4-REF)") (class "Default")
      (node (ref "IC4") (pin "2") (pinfunction "REF_2") (pintype "input"))
      (node (ref "R10") (pin "2") (pinfunction "2_2") (pintype "passive"))
    )
    (net (code "33") (name "Net-(IC5-RBIAS)") (class "Default")
      (node (ref "IC5") (pin "3") (pinfunction "RBIAS_3") (pintype "passive"))
      (node (ref "Q1") (pin "5") (pinfunction "G_5") (pintype "passive"))
      (node (ref "R9") (pin "2") (pinfunction "2_2") (pintype "passive"))
    )
    (net (code "34") (name "Net-(IC5-REF)") (class "Default")
      (node (ref "IC5") (pin "2") (pinfunction "REF_2") (pintype "input"))
      (node (ref "R11") (pin "2") (pinfunction "2_2") (pintype "passive"))
    )
    (net (code "35") (name "Net-(IC6-CPOUT)") (class "Default")
      (node (ref "C21") (pin "2") (pinfunction "2_2") (pintype "passive"))
      (node (ref "IC6") (pin "20") (pinfunction "CPOUT_20") (pintype "output"))
    )
    (net (code "36") (name "Net-(IC6-REGOUT)") (class "Default")
      (node (ref "C20") (pin "1") (pinfunction "1_1") (pintype "passive"))
      (node (ref "IC6") (pin "10") (pinfunction "REGOUT_10") (pintype "output"))
    )
    (net (code "37") (name "Net-(IC6-VCC)") (class "Default")
      (node (ref "C19") (pin "1") (pinfunction "1_1") (pintype "passive"))
      (node (ref "C26") (pin "1") (pinfunction "1_1") (pintype "passive"))
      (node (ref "C28") (pin "1") (pinfunction "1_1") (pintype "passive"))
      (node (ref "IC6") (pin "13") (pinfunction "VCC_13") (pintype "power_in"))
      (node (ref "IC8") (pin "8") (pinfunction "VCC_8") (pintype "power_in"))
      (node (ref "L2") (pin "2") (pinfunction "2_2") (pintype "passive"))
    )
    (net (code "38") (name "Net-(Q2-D)") (class "Default")
      (node (ref "Q2") (pin "3") (pinfunction "D_3") (pintype "passive"))
      (node (ref "X12") (pin "4") (pinfunction "VCC_4") (pintype "power_in"))
    )
    (net (code "39") (name "Net-(Q3-D)") (class "Default")
      (node (ref "Q3") (pin "3") (pinfunction "D_3") (pintype "passive"))
      (node (ref "X10") (pin "1") (pinfunction "1_1") (pintype "passive"))
    )
    (net (code "40") (name "Net-(Q4-D)") (class "Default")
      (node (ref "Q4") (pin "3") (pinfunction "D_3") (pintype "passive"))
      (node (ref "X3") (pin "2") (pinfunction "2_2") (pintype "bidirectional"))
      (node (ref "X5") (pin "2") (pinfunction "2_2") (pintype "bidirectional"))
      (node (ref "X6") (pin "2") (pinfunction "2_2") (pintype "bidirectional"))
    )
    (net (code "41") (name "Net-(Q5-D)") (class "Default")
      (node (ref "Q5") (pin "3") (pinfunction "D_3") (pintype "passive"))
      (node (ref "X4") (pin "2") (pinfunction "2_2") (pintype "bidirectional"))
    )
    (net (code "42") (name "Net-(Q6A-D)") (class "Default")
      (node (ref "D6") (pin "C") (pinfunction "C_C") (pintype "passive"))
      (node (ref "Q6") (pin "6") (pinfunction "D_6") (pintype "passive"))
    )
    (net (code "43") (name "Net-(RN1-Pad5)") (class "Default")
      (node (ref "RN1") (pin "5") (pinfunction "5_5") (pintype "passive"))
      (node (ref "X6") (pin "4") (pinfunction "4_4") (pintype "bidirectional"))
    )
    (net (code "44") (name "Net-(RN1-Pad6)") (class "Default")
      (node (ref "RN1") (pin "6") (pinfunction "6_6") (pintype "passive"))
      (node (ref "X6") (pin "3") (pinfunction "3_3") (pintype "bidirectional"))
    )
    (net (code "45") (name "Net-(RN1-Pad7)") (class "Default")
      (node (ref "RN1") (pin "7") (pinfunction "7_7") (pintype "passive"))
      (node (ref "X5") (pin "4") (pinfunction "4_4") (pintype "bidirectional"))
    )
    (net (code "46") (name "Net-(RN1-Pad8)") (class "Default")
      (node (ref "RN1") (pin "8") (pinfunction "8_8") (pintype "passive"))
      (node (ref "X5") (pin "3") (pinfunction "3_3") (pintype "bidirectional"))
    )
    (net (code "47") (name "Net-(RN3-Pad5)") (class "Default")
      (node (ref "RN3") (pin "5") (pinfunction "5_5") (pintype "passive"))
      (node (ref "X3") (pin "4") (pinfunction "4_4") (pintype "bidirectional"))
    )
    (net (code "48") (name "Net-(RN3-Pad6)") (class "Default")
      (node (ref "RN3") (pin "6") (pinfunction "6_6") (pintype "passive"))
      (node (ref "X3") (pin "3") (pinfunction "3_3") (pintype "bidirectional"))
    )
    (net (code "49") (name "Net-(RN3-Pad7)") (class "Default")
      (node (ref "RN3") (pin "7") (pinfunction "7_7") (pintype "passive"))
      (node (ref "X4") (pin "4") (pinfunction "4_4") (pintype "bidirectional"))
    )
    (net (code "50") (name "Net-(RN3-Pad8)") (class "Default")
      (node (ref "RN3") (pin "8") (pinfunction "8_8") (pintype "passive"))
      (node (ref "X4") (pin "3") (pinfunction "3_3") (pintype "bidirectional"))
    )
    (net (code "51") (name "Net-(RN4-Pad5)") (class "Default")
      (node (ref "RN4") (pin "5") (pinfunction "5_5") (pintype "passive"))
      (node (ref "RN5") (pin "5") (pinfunction "5_5") (pintype "passive"))
      (node (ref "RN5") (pin "6") (pinfunction "6_6") (pintype "passive"))
      (node (ref "X7") (pin "3") (pinfunction "3_3") (pintype "bidirectional"))
      (node (ref "X8") (pin "3") (pinfunction "3_3") (pintype "bidirectional"))
    )
    (net (code "52") (name "Net-(RN4-Pad6)") (class "Default")
      (node (ref "RN4") (pin "6") (pinfunction "6_6") (pintype "passive"))
      (node (ref "RN5") (pin "7") (pinfunction "7_7") (pintype "passive"))
      (node (ref "RN5") (pin "8") (pinfunction "8_8") (pintype "passive"))
      (node (ref "X7") (pin "4") (pinfunction "4_4") (pintype "bidirectional"))
      (node (ref "X8") (pin "4") (pinfunction "4_4") (pintype "bidirectional"))
    )
    (net (code "53") (name "Net-(X1-CC1)") (class "Default")
      (node (ref "R7") (pin "2") (pinfunction "2_2") (pintype "passive"))
      (node (ref "X1") (pin "A5") (pinfunction "CC1_A5") (pintype "passive"))
    )
    (net (code "54") (name "Net-(X1-CC2)") (class "Default")
      (node (ref "R6") (pin "2") (pinfunction "2_2") (pintype "passive"))
      (node (ref "X1") (pin "B5") (pinfunction "CC2_B5") (pintype "passive"))
    )
    (net (code "55") (name "PD_ENABLE") (class "Default")
      (node (ref "D5") (pin "A") (pinfunction "A_A") (pintype "passive"))
      (node (ref "IC3") (pin "25") (pinfunction "IO21_25") (pintype "bidirectional"))
    )
    (net (code "56") (name "PD_SENSE") (class "Default")
      (node (ref "D5") (pin "C") (pinfunction "C_C") (pintype "passive"))
      (node (ref "IC3") (pin "18") (pinfunction "IO14_18") (pintype "bidirectional"))
      (node (ref "R17") (pin "2") (pinfunction "2_2") (pintype "passive"))
    )
    (net (code "57") (name "QWIIC_SCL") (class "Default")
      (node (ref "IC3") (pin "36") (pinfunction "IO40_36") (pintype "bidirectional"))
      (node (ref "RN4") (pin "3") (pinfunction "3_3") (pintype "passive"))
    )
    (net (code "58") (name "QWIIC_SDA") (class "Default")
      (node (ref "IC3") (pin "35") (pinfunction "IO39_35") (pintype "bidirectional"))
      (node (ref "RN4") (pin "4") (pinfunction "4_4") (pintype "passive"))
    )
    (net (code "59") (name "SD_CS") (class "Default")
      (node (ref "IC3") (pin "14") (pinfunction "IO10_14") (pintype "bidirectional"))
      (node (ref "X12") (pin "2") (pinfunction "CD/DAT3_2") (pintype "bidirectional"))
    )
    (net (code "60") (name "SD_ENABLE") (class "Default")
      (node (ref "IC3") (pin "13") (pinfunction "IO9_13") (pintype "bidirectional"))
      (node (ref "Q2") (pin "1") (pinfunction "G_1") (pintype "passive"))
    )
    (net (code "61") (name "SD_MISO") (class "Default")
      (node (ref "IC3") (pin "17") (pinfunction "IO13_17") (pintype "bidirectional"))
      (node (ref "R13") (pin "2") (pinfunction "2_2") (pintype "passive"))
      (node (ref "X12") (pin "7") (pinfunction "DAT0_7") (pintype "bidirectional"))
    )
    (net (code "62") (name "SD_MOSI") (class "Default")
      (node (ref "IC3") (pin "15") (pinfunction "IO11_15") (pintype "bidirectional"))
      (node (ref "X12") (pin "3") (pinfunction "CMD_3") (pintype "input"))
    )
    (net (code "63") (name "SD_SCLK") (class "Default")
      (node (ref "IC3") (pin "16") (pinfunction "IO12_16") (pintype "bidirectional"))
      (node (ref "X12") (pin "5") (pinfunction "CLK_5") (pintype "input"))
    )
    (net (code "64") (name "UART_ENABLE") (class "Default")
      (node (ref "IC3") (pin "26") (pinfunction "IO26_26") (pintype "bidirectional"))
      (node (ref "Q5") (pin "1") (pinfunction "G_1") (pintype "passive"))
      (node (ref "R16") (pin "2") (pinfunction "2_2") (pintype "passive"))
    )
    (net (code "65") (name "UART_RXD") (class "Default")
      (node (ref "IC3") (pin "40") (pinfunction "RXD0_40") (pintype "bidirectional"))
      (node (ref "RN3") (pin "1") (pinfunction "1_1") (pintype "passive"))
    )
    (net (code "66") (name "UART_TXD") (class "Default")
      (node (ref "IC3") (pin "39") (pinfunction "TXD0_39") (pintype "bidirectional"))
      (node (ref "RN3") (pin "2") (pinfunction "2_2") (pintype "passive"))
    )
    (net (code "67") (name "USB_D+") (class "Default")
      (node (ref "IC3") (pin "24") (pinfunction "IO20_24") (pintype "bidirectional"))
      (node (ref "R5") (pin "2") (pinfunction "2_2") (pintype "passive"))
    )
    (net (code "68") (name "USB_D-") (class "Default")
      (node (ref "IC3") (pin "23") (pinfunction "IO19_23") (pintype "bidirectional"))
      (node (ref "R4") (pin "2") (pinfunction "2_2") (pintype "passive"))
    )
    (net (code "69") (name "VBAT") (class "Default")
      (node (ref "C13") (pin "1") (pinfunction "1_1") (pintype "passive"))
      (node (ref "C4") (pin "1") (pinfunction "1_1") (pintype "passive"))
      (node (ref "D2") (pin "6") (pinfunction "VIN2_6") (pintype "power_in"))
      (node (ref "IC2") (pin "3") (pinfunction "VBAT_3") (pintype "bidirectional"))
      (node (ref "IC4") (pin "6") (pinfunction "DRAIN_6") (pintype "passive"))
      (node (ref "Q1") (pin "6") (pinfunction "D_6") (pintype "passive"))
      (node (ref "Q1") (pin "7") (pinfunction "D_7") (pintype "passive"))
      (node (ref "X2") (pin "1") (pinfunction "1_1") (pintype "bidirectional"))
    )
    (net (code "70") (name "VCC_LED") (class "Default")
      (node (ref "C16") (pin "2") (pinfunction "2_2") (pintype "passive"))
      (node (ref "D4") (pin "1") (pinfunction "VCC_1") (pintype "power_in"))
      (node (ref "R12") (pin "1") (pinfunction "1_1") (pintype "passive"))
      (node (ref "RN6") (pin "2") (pinfunction "2_2") (pintype "passive"))
      (node (ref "RN6") (pin "3") (pinfunction "3_3") (pintype "passive"))
      (node (ref "RN6") (pin "4") (pinfunction "4_4") (pintype "passive"))
      (node (ref "SW1") (pin "5") (pinfunction "C2_5") (pintype "bidirectional"))
    )
    (net (code "71") (name "VUSB") (class "Default")
      (node (ref "C12") (pin "1") (pinfunction "1_1") (pintype "passive"))
      (node (ref "C5") (pin "1") (pinfunction "1_1") (pintype "passive"))
      (node (ref "D1") (pin "A") (pinfunction "A_A") (pintype "passive"))
      (node (ref "D2") (pin "3") (pinfunction "VIN1_3") (pintype "power_in"))
      (node (ref "D2") (pin "8") (pinfunction "ST_8") (pintype "open_collector"))
      (node (ref "F1") (pin "2") (pinfunction "3_2") (pintype "passive"))
      (node (ref "IC2") (pin "4") (pinfunction "VIN_4") (pintype "power_in"))
      (node (ref "IC5") (pin "6") (pinfunction "DRAIN_6") (pintype "passive"))
      (node (ref "IC9") (pin "2") (pinfunction "2_2") (pintype "bidirectional"))
      (node (ref "Q1") (pin "3") (pinfunction "D_3") (pintype "passive"))
      (node (ref "Q1") (pin "8") (pinfunction "D_8") (pintype "passive"))
      (node (ref "R18") (pin "2") (pinfunction "2_2") (pintype "passive"))
      (node (ref "SW1") (pin "2") (pinfunction "C1_2") (pintype "bidirectional"))
    )
    (net (code "72") (name "XBEE_CS") (class "Default")
      (node (ref "IC3") (pin "29") (pinfunction "IO34_29") (pintype "bidirectional"))
      (node (ref "X11") (pin "7") (pinfunction "7_7") (pintype "passive"))
    )
    (net (code "73") (name "XBEE_ENABLE") (class "Default")
      (node (ref "IC3") (pin "37") (pinfunction "IO41_37") (pintype "bidirectional"))
      (node (ref "Q3") (pin "1") (pinfunction "G_1") (pintype "passive"))
      (node (ref "R14") (pin "2") (pinfunction "2_2") (pintype "passive"))
    )
    (net (code "74") (name "XBEE_INT") (class "Default")
      (node (ref "IC3") (pin "28") (pinfunction "IO33_28") (pintype "bidirectional"))
      (node (ref "X11") (pin "2") (pinfunction "2_2") (pintype "passive"))
    )
    (net (code "75") (name "XBEE_MISO") (class "Default")
      (node (ref "IC3") (pin "33") (pinfunction "IO37_33") (pintype "bidirectional"))
      (node (ref "X10") (pin "4") (pinfunction "4_4") (pintype "passive"))
    )
    (net (code "76") (name "XBEE_MOSI") (class "Default")
      (node (ref "IC3") (pin "31") (pinfunction "IO35_31") (pintype "bidirectional"))
      (node (ref "X11") (pin "1") (pinfunction "1_1") (pintype "passive"))
    )
    (net (code "77") (name "XBEE_RESET") (class "Default")
      (node (ref "IC3") (pin "34") (pinfunction "IO38_34") (pintype "bidirectional"))
      (node (ref "X10") (pin "5") (pinfunction "5_5") (pintype "passive"))
    )
    (net (code "78") (name "XBEE_RXD") (class "Default")
      (node (ref "IC3") (pin "22") (pinfunction "IO18_22") (pintype "bidirectional"))
      (node (ref "X10") (pin "2") (pinfunction "2_2") (pintype "passive"))
    )
    (net (code "79") (name "XBEE_SCLK") (class "Default")
      (node (ref "IC3") (pin "32") (pinfunction "IO36_32") (pintype "bidirectional"))
      (node (ref "X11") (pin "8") (pinfunction "8_8") (pintype "passive"))
    )
    (net (code "80") (name "XBEE_TXD") (class "Default")
      (node (ref "IC3") (pin "21") (pinfunction "IO17_21") (pintype "bidirectional"))
      (node (ref "X10") (pin "3") (pinfunction "3_3") (pintype "passive"))
    )
    (net (code "81") (name "unconnected-(D4-DOUT-Pad2)") (class "Default")
      (node (ref "D4") (pin "2") (pinfunction "DOUT_2") (pintype "output"))
    )
    (net (code "82") (name "unconnected-(IC6-AUX_CL-Pad7)") (class "Default")
      (node (ref "IC6") (pin "7") (pinfunction "AUX_CL_7") (pintype "bidirectional"))
    )
    (net (code "83") (name "unconnected-(IC6-AUX_DA-Pad6)") (class "Default")
      (node (ref "IC6") (pin "6") (pinfunction "AUX_DA_6") (pintype "bidirectional"))
    )
    (net (code "84") (name "unconnected-(IC8-INT2-Pad9)") (class "Default")
      (node (ref "IC8") (pin "9") (pinfunction "INT2_9") (pintype "output"))
    )
    (net (code "85") (name "unconnected-(RN4-Pad1)") (class "Default")
      (node (ref "RN4") (pin "1") (pinfunction "1_1") (pintype "passive"))
    )
    (net (code "86") (name "unconnected-(RN4-Pad2)") (class "Default")
      (node (ref "RN4") (pin "2") (pinfunction "2_2") (pintype "passive"))
    )
    (net (code "87") (name "unconnected-(RN4-Pad7)") (class "Default")
      (node (ref "RN4") (pin "7") (pinfunction "7_7") (pintype "passive"))
    )
    (net (code "88") (name "unconnected-(RN4-Pad8)") (class "Default")
      (node (ref "RN4") (pin "8") (pinfunction "8_8") (pintype "passive"))
    )
    (net (code "89") (name "unconnected-(RN6-Pad5)") (class "Default")
      (node (ref "RN6") (pin "5") (pinfunction "5_5") (pintype "passive"))
    )
    (net (code "90") (name "unconnected-(RN6-Pad6)") (class "Default")
      (node (ref "RN6") (pin "6") (pinfunction "6_6") (pintype "passive"))
    )
    (net (code "91") (name "unconnected-(SW1-NO1-Pad1)") (class "Default")
      (node (ref "SW1") (pin "1") (pinfunction "NO1_1") (pintype "bidirectional"))
    )
    (net (code "92") (name "unconnected-(X10-Pad6)") (class "Default")
      (node (ref "X10") (pin "6") (pinfunction "6_6") (pintype "passive"))
    )
    (net (code "93") (name "unconnected-(X10-Pad7)") (class "Default")
      (node (ref "X10") (pin "7") (pinfunction "7_7") (pintype "passive"))
    )
    (net (code "94") (name "unconnected-(X10-Pad8)") (class "Default")
      (node (ref "X10") (pin "8") (pinfunction "8_8") (pintype "passive"))
    )
    (net (code "95") (name "unconnected-(X10-Pad9)") (class "Default")
      (node (ref "X10") (pin "9") (pinfunction "9_9") (pintype "passive"))
    )
    (net (code "96") (name "unconnected-(X11-Pad3)") (class "Default")
      (node (ref "X11") (pin "3") (pinfunction "3_3") (pintype "passive"))
    )
    (net (code "97") (name "unconnected-(X11-Pad4)") (class "Default")
      (node (ref "X11") (pin "4") (pinfunction "4_4") (pintype "passive"))
    )
    (net (code "98") (name "unconnected-(X11-Pad5)") (class "Default")
      (node (ref "X11") (pin "5") (pinfunction "5_5") (pintype "passive"))
    )
    (net (code "99") (name "unconnected-(X11-Pad6)") (class "Default")
      (node (ref "X11") (pin "6") (pinfunction "6_6") (pintype "passive"))
    )
    (net (code "100") (name "unconnected-(X11-Pad9)") (class "Default")
      (node (ref "X11") (pin "9") (pinfunction "9_9") (pintype "passive"))
    )
    (net (code "101") (name "unconnected-(X11-Pad10)") (class "Default")
      (node (ref "X11") (pin "10") (pinfunction "10_10") (pintype "passive"))
    )
    (net (code "102") (name "unconnected-(X12-CD-Pad9)") (class "Default")
      (node (ref "X12") (pin "9") (pinfunction "CD_9") (pintype "passive"))
    )
    (net (code "103") (name "unconnected-(X12-DAT1-Pad8)") (class "Default")
      (node (ref "X12") (pin "8") (pinfunction "DAT1_8") (pintype "bidirectional"))
    )
    (net (code "104") (name "unconnected-(X12-DAT2-Pad1)") (class "Default")
      (node (ref "X12") (pin "1") (pinfunction "DAT2_1") (pintype "bidirectional"))
    )
  )
)
